# SCH_GSME_voltmeter_Arduino_ESP8266_TP405.net
KiCad netlist of a schematic drawn in EasyEDA
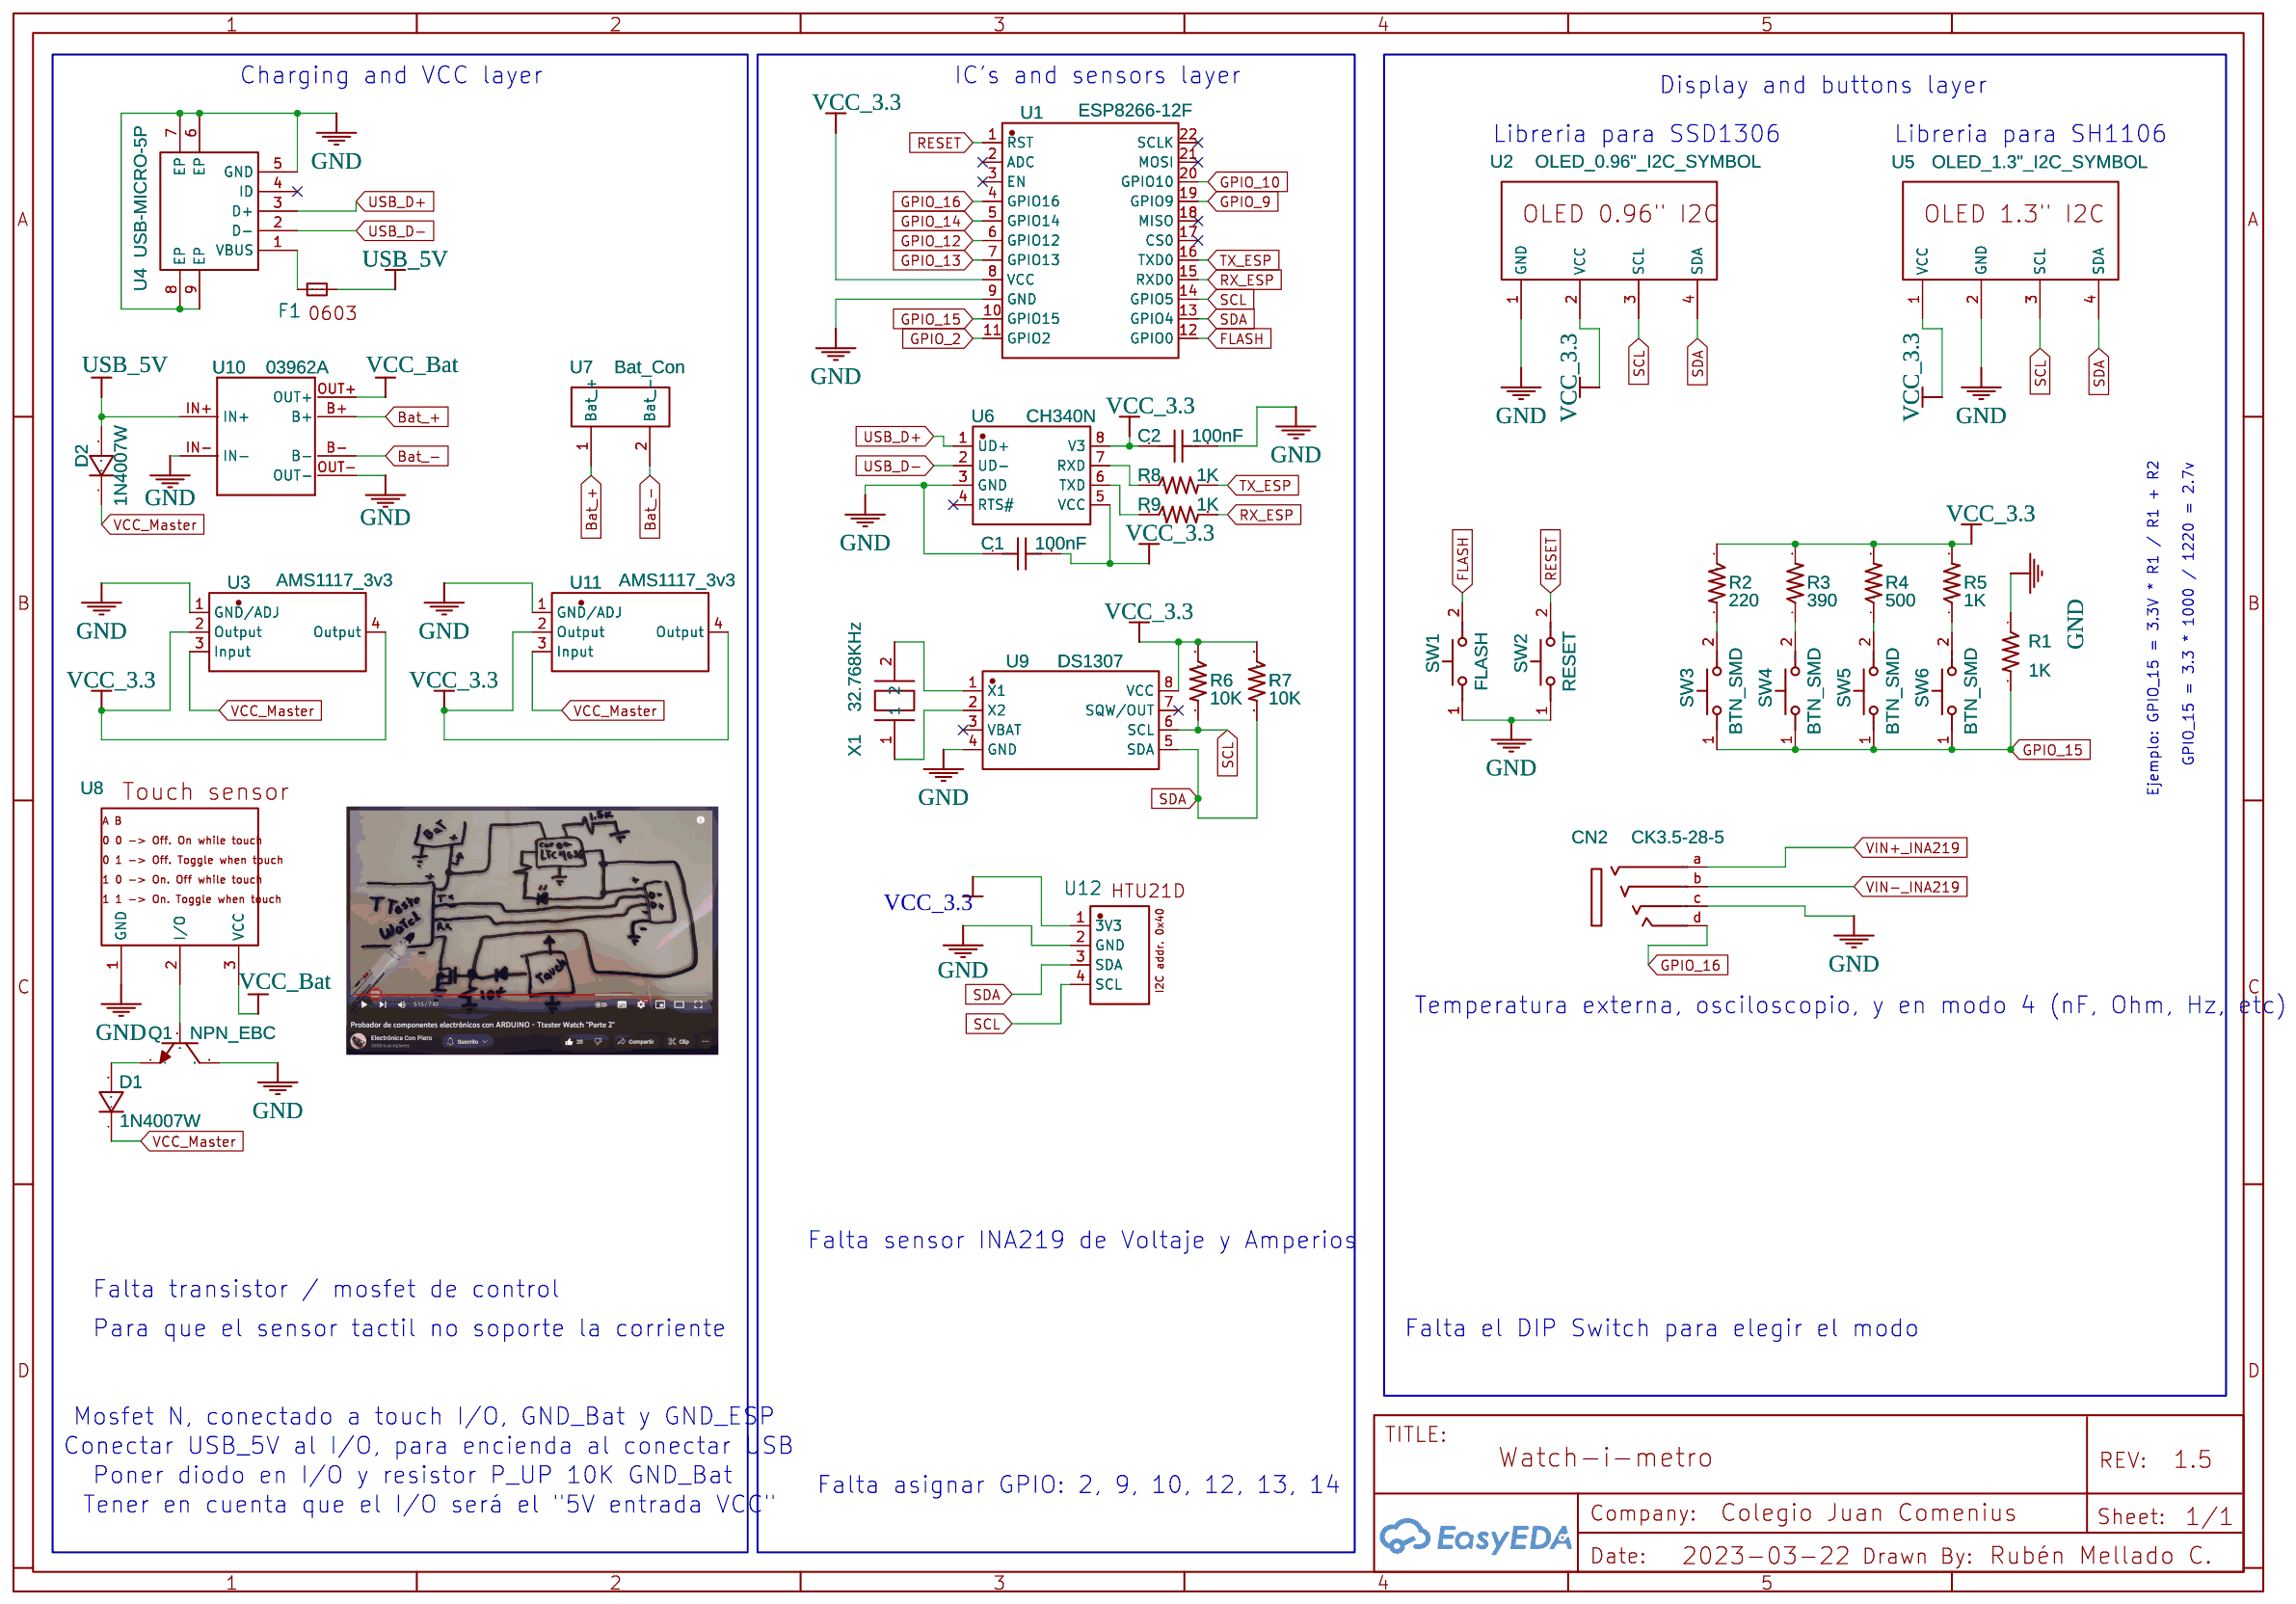
[diagram p0: schematic sheet]

(export (version "E")
  (design (tool "Eeschema 10.0.6"))
  (components
    (comp (ref "C1") (value "100nF") (libsource (lib "") (part "C_0603_US")))
    (comp (ref "C2") (value "100nF") (libsource (lib "") (part "C_0603_US")))
    (comp (ref "CN2")
      (value "CK3.5-28-5")
      (fields (field (name "BOM_Supplier Part") "C718048"))
      (libsource (lib "") (part "CK3.5-28-5"))
    )
    (comp (ref "D1")
      (value "1N4007W")
      (fields (field (name "BOM_Supplier Part") "C328592"))
      (libsource (lib "") (part "1N4007W"))
    )
    (comp (ref "D2")
      (value "1N4007W")
      (fields (field (name "BOM_Supplier Part") "C328592"))
      (libsource (lib "") (part "1N4007W"))
    )
    (comp (ref "F1")
      (value "Fuse")
      (fields (field (name "BOM_Manufacturer Part") "0603") (field (name "BOM_Supplier Part") "C9900014602"))
      (libsource (lib "") (part "0603_FUSE_SYMBOL"))
    )
    (comp (ref "Q1")
      (value "NPN_EBC")
      (fields
        (field (name "BOM_Manufacturer Part") "2n3904S-RTK/PS")
        (field (name "BOM_Supplier Part") "C18536")
      )
      (libsource (lib "") (part "2N3904(SOT-23)"))
    )
    (comp (ref "R1") (value "1K") (libsource (lib "") (part "RESISTOR0603_1")))
    (comp (ref "R2") (value "220") (libsource (lib "") (part "RESISTOR0603_1")))
    (comp (ref "R3") (value "390") (libsource (lib "") (part "RESISTOR0603")))
    (comp (ref "R4") (value "500") (libsource (lib "") (part "RESISTOR0603")))
    (comp (ref "R5") (value "1K") (libsource (lib "") (part "RESISTOR0603")))
    (comp (ref "R6") (value "10K") (libsource (lib "") (part "RESISTOR0603_1")))
    (comp (ref "R7") (value "10K") (libsource (lib "") (part "RESISTOR0603_1")))
    (comp (ref "R8") (value "1K") (libsource (lib "") (part "RESISTOR0603_2")))
    (comp (ref "R9") (value "1K") (libsource (lib "") (part "RESISTOR0603_2")))
    (comp (ref "SW1")
      (value "FLASH")
      (fields
        (field (name "BOM_Manufacturer Part") "BUTTON2")
        (field (name "BOM_Supplier Part") "C9900005988")
      )
      (libsource (lib "") (part "BUTTON2"))
    )
    (comp (ref "SW2")
      (value "RESET")
      (fields
        (field (name "BOM_Manufacturer Part") "BUTTON2")
        (field (name "BOM_Supplier Part") "C9900005988")
      )
      (libsource (lib "") (part "BUTTON2"))
    )
    (comp (ref "SW3")
      (value "BTN_SMD")
      (fields
        (field (name "BOM_Manufacturer Part") "BUTTON2")
        (field (name "BOM_Supplier Part") "C9900005988")
      )
      (libsource (lib "") (part "BUTTON2"))
    )
    (comp (ref "SW4")
      (value "BTN_SMD")
      (fields
        (field (name "BOM_Manufacturer Part") "BUTTON2")
        (field (name "BOM_Supplier Part") "C9900005988")
      )
      (libsource (lib "") (part "BUTTON2"))
    )
    (comp (ref "SW5")
      (value "BTN_SMD")
      (fields
        (field (name "BOM_Manufacturer Part") "BUTTON2")
        (field (name "BOM_Supplier Part") "C9900005988")
      )
      (libsource (lib "") (part "BUTTON2"))
    )
    (comp (ref "SW6")
      (value "BTN_SMD")
      (fields
        (field (name "BOM_Manufacturer Part") "BUTTON2")
        (field (name "BOM_Supplier Part") "C9900005988")
      )
      (libsource (lib "") (part "BUTTON2"))
    )
    (comp (ref "U1")
      (value "ESP8266-12F")
      (fields
        (field (name "BOM_Manufacturer Part") "ESP-12F(ESP8266MOD)")
        (field (name "BOM_Supplier Part") "C82891")
      )
      (libsource (lib "") (part "ESP-12F(ESP8266MOD)"))
    )
    (comp (ref "U2")
      (value "OLED_0.96\"_I2C_SYMBOL")
      (libsource (lib "") (part "OLED_0.96{dblquote}_I2C_SYMBOL"))
    )
    (comp (ref "U3")
      (value "AMS1117_3v3")
      (fields
        (field (name "BOM_Manufacturer Part") "AMS1117-3.3S")
        (field (name "BOM_Supplier Part") "C2842296")
      )
      (libsource (lib "") (part "AMS1117-3.3S"))
    )
    (comp (ref "U4")
      (value "USB-MICRO-5P")
      (fields
        (field (name "BOM_Manufacturer Part") "USB-Micro-5P")
        (field (name "BOM_Supplier Part") "C9900014288")
      )
      (libsource (lib "") (part "USB-MICRO-5P"))
    )
    (comp (ref "U5")
      (value "OLED_1.3\"_I2C_SYMBOL")
      (libsource (lib "") (part "OLED_1.3{dblquote}_I2C_SYMBOL"))
    )
    (comp (ref "U6")
      (value "CH340N")
      (fields (field (name "BOM_Supplier Part") "C506813"))
      (libsource (lib "") (part "CH340N"))
    )
    (comp (ref "U7") (value "Bat_Con") (libsource (lib "") (part "Connector_Battery_2_Wires_2p")))
    (comp (ref "U8") (value "Touch_Sensor") (libsource (lib "") (part "Touch_Sensor_3p_A_B_SYMBOL")))
    (comp (ref "U9")
      (value "DS1307")
      (fields
        (field (name "BOM_Manufacturer Part") "DS1307M/TR")
        (field (name "BOM_Supplier Part") "C356706")
      )
      (libsource (lib "") (part "DS1307M/TR"))
    )
    (comp (ref "U10") (value "03962A") (libsource (lib "") (part "03962A")))
    (comp (ref "U11")
      (value "AMS1117_3v3")
      (fields
        (field (name "BOM_Manufacturer Part") "AMS1117-3.3S")
        (field (name "BOM_Supplier Part") "C2842296")
      )
      (libsource (lib "") (part "AMS1117-3.3S"))
    )
    (comp (ref "U12") (value "HTU21D") (libsource (lib "") (part "SF HTU21D HUMIDITY")))
    (comp (ref "X1") (value "32.768KHz") (libsource (lib "") (part "Quartz_X_2p_Symbol")))
  )
  (nets
    (net (code "1") (name "Bat_+") (class "Default")
      (node (ref "U10") (pin "B+") (pinfunction "B+_B+") (pintype "bidirectional"))
      (node (ref "U7") (pin "1") (pinfunction "Bat_+_1") (pintype "unspecified"))
    )
    (net (code "2") (name "Bat_-") (class "Default")
      (node (ref "U10") (pin "B-") (pinfunction "B-_B-") (pintype "bidirectional"))
      (node (ref "U7") (pin "2") (pinfunction "Bat_-_2") (pintype "unspecified"))
    )
    (net (code "3") (name "FLASH") (class "Default")
      (node (ref "SW1") (pin "2") (pinfunction "2_2") (pintype "unspecified"))
      (node (ref "U1") (pin "12") (pinfunction "GPIO0_12") (pintype "unspecified"))
    )
    (net (code "4") (name "GND") (class "Default")
      (node (ref "C1") (pin "1") (pinfunction "1_1") (pintype "unspecified"))
      (node (ref "C2") (pin "2") (pinfunction "2_2") (pintype "unspecified"))
      (node (ref "CN2") (pin "c") (pinfunction "c_c") (pintype "unspecified"))
      (node (ref "Q1") (pin "2") (pinfunction "C_2") (pintype "input"))
      (node (ref "R1") (pin "1") (pinfunction "1_1") (pintype "unspecified"))
      (node (ref "SW1") (pin "1") (pinfunction "1_1") (pintype "unspecified"))
      (node (ref "SW2") (pin "1") (pinfunction "1_1") (pintype "unspecified"))
      (node (ref "U1") (pin "9") (pinfunction "GND_9") (pintype "unspecified"))
      (node (ref "U10") (pin "IN-") (pinfunction "IN-_IN-") (pintype "bidirectional"))
      (node (ref "U10") (pin "OUT-") (pinfunction "OUT-_OUT-") (pintype "bidirectional"))
      (node (ref "U11") (pin "1") (pinfunction "GND/ADJ_1") (pintype "unspecified"))
      (node (ref "U12") (pin "2") (pinfunction "GND_2") (pintype "unspecified"))
      (node (ref "U2") (pin "1") (pinfunction "GND_1") (pintype "unspecified"))
      (node (ref "U3") (pin "1") (pinfunction "GND/ADJ_1") (pintype "unspecified"))
      (node (ref "U4") (pin "5") (pinfunction "GND_5") (pintype "unspecified"))
      (node (ref "U4") (pin "6") (pinfunction "EP_6") (pintype "unspecified"))
      (node (ref "U4") (pin "7") (pinfunction "EP_7") (pintype "unspecified"))
      (node (ref "U4") (pin "8") (pinfunction "EP_8") (pintype "unspecified"))
      (node (ref "U4") (pin "9") (pinfunction "EP_9") (pintype "unspecified"))
      (node (ref "U5") (pin "2") (pinfunction "GND_2") (pintype "unspecified"))
      (node (ref "U6") (pin "3") (pinfunction "GND_3") (pintype "unspecified"))
      (node (ref "U8") (pin "1") (pinfunction "GND_1") (pintype "unspecified"))
      (node (ref "U9") (pin "4") (pinfunction "GND_4") (pintype "unspecified"))
    )
    (net (code "5") (name "GPIO_2") (class "Default")
      (node (ref "U1") (pin "11") (pinfunction "GPIO2_11") (pintype "unspecified"))
    )
    (net (code "6") (name "GPIO_9") (class "Default")
      (node (ref "U1") (pin "19") (pinfunction "GPIO9_19") (pintype "unspecified"))
    )
    (net (code "7") (name "GPIO_10") (class "Default")
      (node (ref "U1") (pin "20") (pinfunction "GPIO10_20") (pintype "unspecified"))
    )
    (net (code "8") (name "GPIO_12") (class "Default")
      (node (ref "U1") (pin "6") (pinfunction "GPIO12_6") (pintype "unspecified"))
    )
    (net (code "9") (name "GPIO_13") (class "Default")
      (node (ref "U1") (pin "7") (pinfunction "GPIO13_7") (pintype "unspecified"))
    )
    (net (code "10") (name "GPIO_14") (class "Default")
      (node (ref "U1") (pin "5") (pinfunction "GPIO14_5") (pintype "unspecified"))
    )
    (net (code "11") (name "GPIO_15") (class "Default")
      (node (ref "R1") (pin "2") (pinfunction "2_2") (pintype "unspecified"))
      (node (ref "SW3") (pin "1") (pinfunction "1_1") (pintype "unspecified"))
      (node (ref "SW4") (pin "1") (pinfunction "1_1") (pintype "unspecified"))
      (node (ref "SW5") (pin "1") (pinfunction "1_1") (pintype "unspecified"))
      (node (ref "SW6") (pin "1") (pinfunction "1_1") (pintype "unspecified"))
      (node (ref "U1") (pin "10") (pinfunction "GPIO15_10") (pintype "unspecified"))
    )
    (net (code "12") (name "GPIO_16") (class "Default")
      (node (ref "CN2") (pin "d") (pinfunction "d_d") (pintype "unspecified"))
      (node (ref "U1") (pin "4") (pinfunction "GPIO16_4") (pintype "unspecified"))
    )
    (net (code "13") (name "Net-(F1-K)") (class "Default")
      (node (ref "F1") (pin "1") (pinfunction "K_1") (pintype "unspecified"))
      (node (ref "U4") (pin "1") (pinfunction "VBUS_1") (pintype "unspecified"))
    )
    (net (code "14") (name "Net-(Q1-B)") (class "Default")
      (node (ref "Q1") (pin "3") (pinfunction "B_3") (pintype "input"))
      (node (ref "U8") (pin "2") (pinfunction "I/O_2") (pintype "unspecified"))
    )
    (net (code "15") (name "Net-(Q1-E)") (class "Default")
      (node (ref "D1") (pin "2") (pinfunction "2_2") (pintype "unspecified"))
      (node (ref "Q1") (pin "1") (pinfunction "E_1") (pintype "input"))
    )
    (net (code "16") (name "Net-(R2-Pad2)") (class "Default")
      (node (ref "R2") (pin "2") (pinfunction "2_2") (pintype "unspecified"))
      (node (ref "SW3") (pin "2") (pinfunction "2_2") (pintype "unspecified"))
    )
    (net (code "17") (name "Net-(R3-Pad1)") (class "Default")
      (node (ref "R3") (pin "1") (pinfunction "1_1") (pintype "unspecified"))
      (node (ref "SW4") (pin "2") (pinfunction "2_2") (pintype "unspecified"))
    )
    (net (code "18") (name "Net-(R4-Pad1)") (class "Default")
      (node (ref "R4") (pin "1") (pinfunction "1_1") (pintype "unspecified"))
      (node (ref "SW5") (pin "2") (pinfunction "2_2") (pintype "unspecified"))
    )
    (net (code "19") (name "Net-(R5-Pad1)") (class "Default")
      (node (ref "R5") (pin "1") (pinfunction "1_1") (pintype "unspecified"))
      (node (ref "SW6") (pin "2") (pinfunction "2_2") (pintype "unspecified"))
    )
    (net (code "20") (name "Net-(U6-RXD)") (class "Default")
      (node (ref "R8") (pin "1") (pinfunction "1_1") (pintype "unspecified"))
      (node (ref "U6") (pin "7") (pinfunction "RXD_7") (pintype "unspecified"))
    )
    (net (code "21") (name "Net-(U6-TXD)") (class "Default")
      (node (ref "R9") (pin "1") (pinfunction "1_1") (pintype "unspecified"))
      (node (ref "U6") (pin "6") (pinfunction "TXD_6") (pintype "unspecified"))
    )
    (net (code "22") (name "Net-(U9-X1)") (class "Default")
      (node (ref "U9") (pin "1") (pinfunction "X1_1") (pintype "unspecified"))
      (node (ref "X1") (pin "2") (pinfunction "2_2") (pintype "unspecified"))
    )
    (net (code "23") (name "Net-(U9-X2)") (class "Default")
      (node (ref "U9") (pin "2") (pinfunction "X2_2") (pintype "unspecified"))
      (node (ref "X1") (pin "1") (pinfunction "1_1") (pintype "unspecified"))
    )
    (net (code "24") (name "RESET") (class "Default")
      (node (ref "SW2") (pin "2") (pinfunction "2_2") (pintype "unspecified"))
      (node (ref "U1") (pin "1") (pinfunction "RST_1") (pintype "unspecified"))
    )
    (net (code "25") (name "RX_ESP") (class "Default")
      (node (ref "R9") (pin "2") (pinfunction "2_2") (pintype "unspecified"))
      (node (ref "U1") (pin "15") (pinfunction "RXD0_15") (pintype "unspecified"))
    )
    (net (code "26") (name "SCL") (class "Default")
      (node (ref "R6") (pin "2") (pinfunction "2_2") (pintype "unspecified"))
      (node (ref "U1") (pin "14") (pinfunction "GPIO5_14") (pintype "unspecified"))
      (node (ref "U12") (pin "4") (pinfunction "SCL_4") (pintype "unspecified"))
      (node (ref "U2") (pin "3") (pinfunction "SCL_3") (pintype "unspecified"))
      (node (ref "U5") (pin "3") (pinfunction "SCL_3") (pintype "unspecified"))
      (node (ref "U9") (pin "6") (pinfunction "SCL_6") (pintype "unspecified"))
    )
    (net (code "27") (name "SDA") (class "Default")
      (node (ref "R7") (pin "2") (pinfunction "2_2") (pintype "unspecified"))
      (node (ref "U1") (pin "13") (pinfunction "GPIO4_13") (pintype "unspecified"))
      (node (ref "U12") (pin "3") (pinfunction "SDA_3") (pintype "unspecified"))
      (node (ref "U2") (pin "4") (pinfunction "SDA_4") (pintype "unspecified"))
      (node (ref "U5") (pin "4") (pinfunction "SDA_4") (pintype "unspecified"))
      (node (ref "U9") (pin "5") (pinfunction "SDA_5") (pintype "unspecified"))
    )
    (net (code "28") (name "TX_ESP") (class "Default")
      (node (ref "R8") (pin "2") (pinfunction "2_2") (pintype "unspecified"))
      (node (ref "U1") (pin "16") (pinfunction "TXD0_16") (pintype "unspecified"))
    )
    (net (code "29") (name "USB_5V") (class "Default")
      (node (ref "D2") (pin "2") (pinfunction "2_2") (pintype "unspecified"))
      (node (ref "F1") (pin "2") (pinfunction "A_2") (pintype "unspecified"))
      (node (ref "U10") (pin "IN+") (pinfunction "IN+_IN+") (pintype "bidirectional"))
    )
    (net (code "30") (name "USB_D+") (class "Default")
      (node (ref "U4") (pin "3") (pinfunction "D+_3") (pintype "unspecified"))
      (node (ref "U6") (pin "1") (pinfunction "UD+_1") (pintype "unspecified"))
    )
    (net (code "31") (name "USB_D-") (class "Default")
      (node (ref "U4") (pin "2") (pinfunction "D-_2") (pintype "unspecified"))
      (node (ref "U6") (pin "2") (pinfunction "UD-_2") (pintype "unspecified"))
    )
    (net (code "32") (name "VCC_3.3") (class "Default")
      (node (ref "C1") (pin "2") (pinfunction "2_2") (pintype "unspecified"))
      (node (ref "C2") (pin "1") (pinfunction "1_1") (pintype "unspecified"))
      (node (ref "R2") (pin "1") (pinfunction "1_1") (pintype "unspecified"))
      (node (ref "R3") (pin "2") (pinfunction "2_2") (pintype "unspecified"))
      (node (ref "R4") (pin "2") (pinfunction "2_2") (pintype "unspecified"))
      (node (ref "R5") (pin "2") (pinfunction "2_2") (pintype "unspecified"))
      (node (ref "R6") (pin "1") (pinfunction "1_1") (pintype "unspecified"))
      (node (ref "R7") (pin "1") (pinfunction "1_1") (pintype "unspecified"))
      (node (ref "U1") (pin "8") (pinfunction "VCC_8") (pintype "unspecified"))
      (node (ref "U11") (pin "2") (pinfunction "Output_2") (pintype "unspecified"))
      (node (ref "U11") (pin "4") (pinfunction "Output_4") (pintype "unspecified"))
      (node (ref "U12") (pin "1") (pinfunction "3V3_1") (pintype "unspecified"))
      (node (ref "U2") (pin "2") (pinfunction "VCC_2") (pintype "unspecified"))
      (node (ref "U3") (pin "2") (pinfunction "Output_2") (pintype "unspecified"))
      (node (ref "U3") (pin "4") (pinfunction "Output_4") (pintype "unspecified"))
      (node (ref "U5") (pin "1") (pinfunction "VCC_1") (pintype "unspecified"))
      (node (ref "U6") (pin "5") (pinfunction "VCC_5") (pintype "unspecified"))
      (node (ref "U6") (pin "8") (pinfunction "V3_8") (pintype "unspecified"))
      (node (ref "U9") (pin "8") (pinfunction "VCC_8") (pintype "unspecified"))
    )
    (net (code "33") (name "VCC_Bat") (class "Default")
      (node (ref "U10") (pin "OUT+") (pinfunction "OUT+_OUT+") (pintype "bidirectional"))
      (node (ref "U8") (pin "3") (pinfunction "VCC_3") (pintype "unspecified"))
    )
    (net (code "34") (name "VCC_Master") (class "Default")
      (node (ref "D1") (pin "1") (pinfunction "1_1") (pintype "unspecified"))
      (node (ref "D2") (pin "1") (pinfunction "1_1") (pintype "unspecified"))
      (node (ref "U11") (pin "3") (pinfunction "Input_3") (pintype "unspecified"))
      (node (ref "U3") (pin "3") (pinfunction "Input_3") (pintype "unspecified"))
    )
    (net (code "35") (name "VIN+_INA219") (class "Default")
      (node (ref "CN2") (pin "a") (pinfunction "a_a") (pintype "unspecified"))
    )
    (net (code "36") (name "VIN-_INA219") (class "Default")
      (node (ref "CN2") (pin "b") (pinfunction "b_b") (pintype "unspecified"))
    )
    (net (code "37") (name "unconnected-(U1-ADC-Pad2)") (class "Default")
      (node (ref "U1") (pin "2") (pinfunction "ADC_2") (pintype "unspecified+no_connect"))
    )
    (net (code "38") (name "unconnected-(U1-CS0-Pad17)") (class "Default")
      (node (ref "U1") (pin "17") (pinfunction "CS0_17") (pintype "unspecified+no_connect"))
    )
    (net (code "39") (name "unconnected-(U1-EN-Pad3)") (class "Default")
      (node (ref "U1") (pin "3") (pinfunction "EN_3") (pintype "unspecified+no_connect"))
    )
    (net (code "40") (name "unconnected-(U1-MISO-Pad18)") (class "Default")
      (node (ref "U1") (pin "18") (pinfunction "MISO_18") (pintype "unspecified+no_connect"))
    )
    (net (code "41") (name "unconnected-(U1-MOSI-Pad21)") (class "Default")
      (node (ref "U1") (pin "21") (pinfunction "MOSI_21") (pintype "unspecified+no_connect"))
    )
    (net (code "42") (name "unconnected-(U1-SCLK-Pad22)") (class "Default")
      (node (ref "U1") (pin "22") (pinfunction "SCLK_22") (pintype "unspecified+no_connect"))
    )
    (net (code "43") (name "unconnected-(U4-ID-Pad4)") (class "Default")
      (node (ref "U4") (pin "4") (pinfunction "ID_4") (pintype "unspecified+no_connect"))
    )
    (net (code "44") (name "unconnected-(U6-RTS#-Pad4)") (class "Default")
      (node (ref "U6") (pin "4") (pinfunction "RTS#_4") (pintype "unspecified+no_connect"))
    )
    (net (code "45") (name "unconnected-(U9-SQW{slash}OUT-Pad7)") (class "Default")
      (node (ref "U9") (pin "7") (pinfunction "SQW/OUT_7") (pintype "unspecified+no_connect"))
    )
    (net (code "46") (name "unconnected-(U9-VBAT-Pad3)") (class "Default")
      (node (ref "U9") (pin "3") (pinfunction "VBAT_3") (pintype "unspecified+no_connect"))
    )
  )
)
